# Reefing-BM.net
KiCad netlist of a schematic drawn in Altium Designer
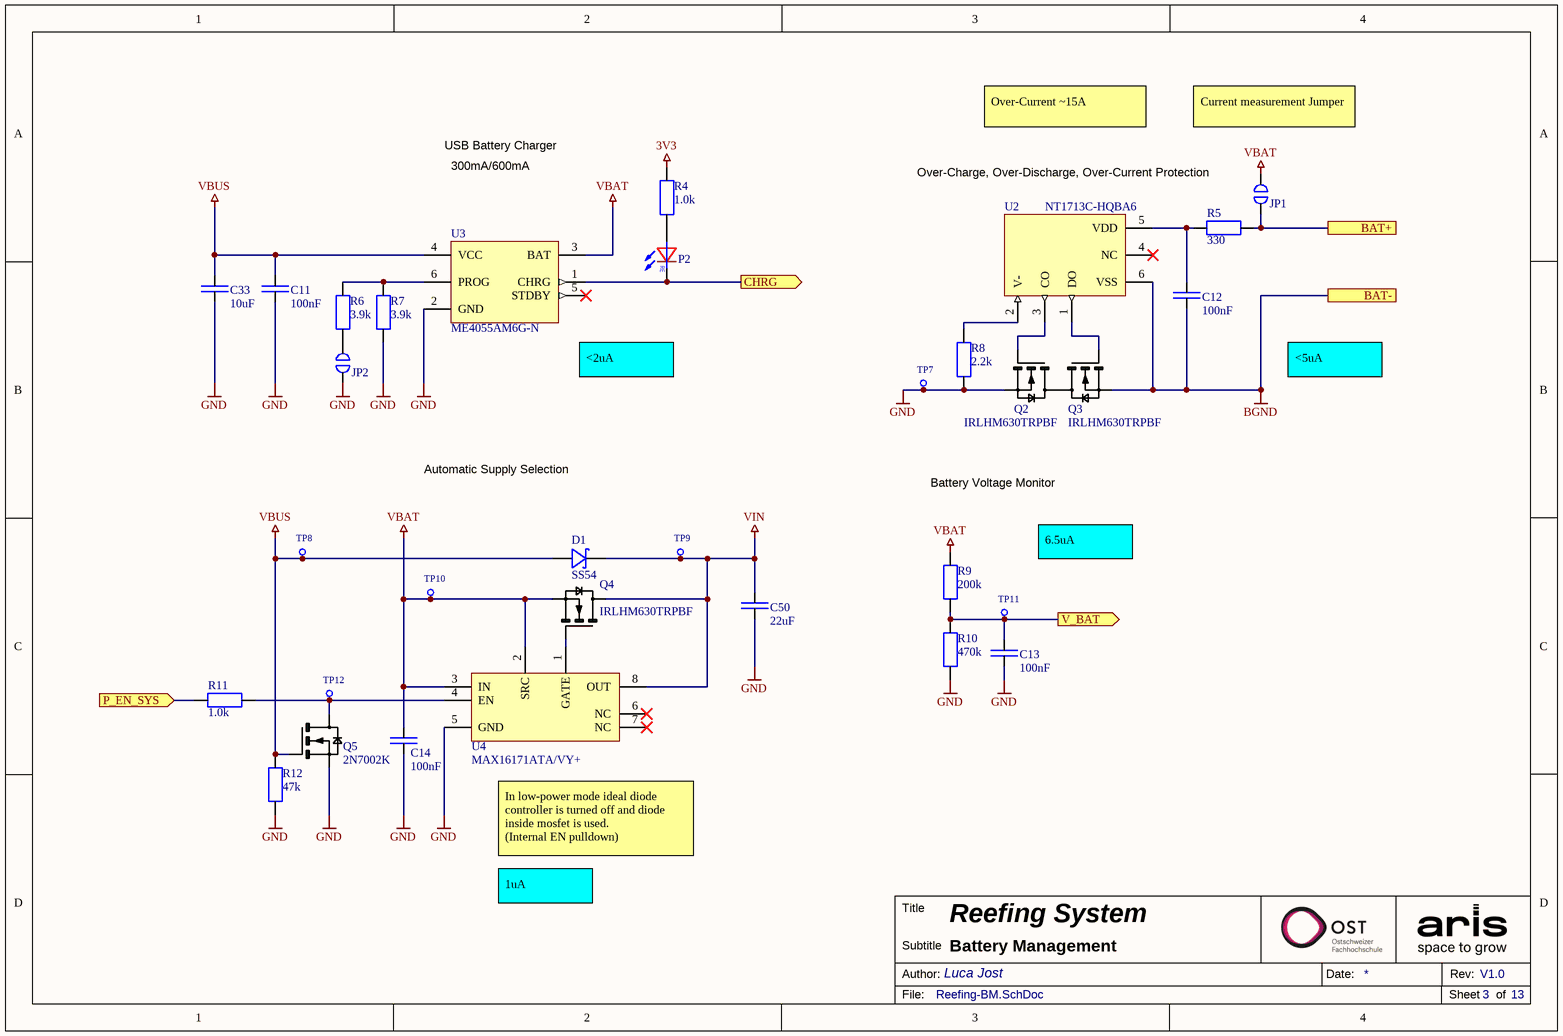
[diagram p0: Reefing-BM.SchDoc]

(export (version "E")
  (design (tool "Eeschema 10.0.6"))
  (components
    (comp (ref "C11")
      (value "100nF")
      (footprint "SMD Keramikkondensator 0402")
      (description "SMD Ceramic Capacitor E6")
      (libsource (lib "Ceramic Capacitors-E6") (part "E6 - 100nF"))
    )
    (comp (ref "C12")
      (value "100nF")
      (footprint "SMD Keramikkondensator 0402")
      (description "SMD Ceramic Capacitor E6")
      (libsource (lib "Ceramic Capacitors-E6") (part "E6 - 100nF"))
    )
    (comp (ref "C13")
      (value "100nF")
      (footprint "SMD Keramikkondensator 0402")
      (description "SMD Ceramic Capacitor E6")
      (libsource (lib "Ceramic Capacitors-E6") (part "E6 - 100nF"))
    )
    (comp (ref "C14")
      (value "100nF")
      (footprint "SMD Keramikkondensator 0402")
      (description "SMD Ceramic Capacitor E6")
      (libsource (lib "Ceramic Capacitors-E6") (part "E6 - 100nF"))
    )
    (comp (ref "C33")
      (value "10uF")
      (footprint "SMD Keramikkondensator 0603")
      (description "SMD Ceramic Capacitor E6")
      (libsource (lib "Ceramic Capacitors-E6") (part "E6 - 10uF"))
    )
    (comp (ref "C50")
      (value "22uF")
      (footprint "SMD Keramikkondensator 0805")
      (description "SMD Ceramic Capacitor E6")
      (libsource (lib "Ceramic Capacitors-E6") (part "E6 - 22uF"))
    )
    (comp (ref "D1")
      (value "SS54")
      (footprint "SMD Diode DO-214-AC")
      (description "40V 5A 550mV @ 5A SMA(DO-214AC) Schottky Barrier Diodes (SBD) ROHS")
      (libsource (lib "Diodes") (part "SS54"))
    )
    (comp (ref "JP1")
      (value "Jumper")
      (footprint "SMD Solder Jumper 1x2mm")
      (description "Single Position Jumper")
      (libsource (lib "Connectors") (part "Jumper-1"))
    )
    (comp (ref "JP2")
      (value "Jumper")
      (footprint "SMD Solder Jumper 1x2mm")
      (description "Single Position Jumper")
      (libsource (lib "Connectors") (part "Jumper-1"))
    )
    (comp (ref "P2")
      (value "LED")
      (footprint "SMD LED 0603")
      (description "Color LED")
      (libsource (lib "Diodes") (part "LED"))
    )
    (comp (ref "Q2")
      (value "IRLHM630TRPBF")
      (footprint "SMD MOSFET DFN 3.3x3.3")
      (description "N-Channel 30V 21A 3.5mOhm@4.5V")
      (libsource (lib "") (part "IRLHM630TRPBF_1"))
    )
    (comp (ref "Q3")
      (value "IRLHM630TRPBF")
      (footprint "SMD MOSFET DFN 3.3x3.3")
      (description "N-Channel 30V 21A 3.5mOhm@4.5V")
      (libsource (lib "Reefing System") (part "IRLHM630TRPBF"))
    )
    (comp (ref "Q4")
      (value "IRLHM630TRPBF")
      (footprint "SMD MOSFET DFN 3.3x3.3")
      (description "N-Channel 30V 21A 3.5mOhm@4.5V")
      (libsource (lib "") (part "IRLHM630TRPBF_2"))
    )
    (comp (ref "Q5")
      (value "2N7002K")
      (footprint "SMD MOSFET SOT-23")
      (description "MOSFET N-Channel 60V / 500mA")
      (libsource (lib "Electronic Switches") (part "2N7002K"))
    )
    (comp (ref "R4")
      (value "1.0k")
      (footprint "SMD Widerstand 0402")
      (description "SMD Chip Resistor E24")
      (libsource (lib "") (part "E24 - 1.0k_1"))
    )
    (comp (ref "R5")
      (value "330")
      (footprint "SMD Widerstand 0402")
      (description "SMD Chip Resistor E24")
      (libsource (lib "Resistors-E24") (part "E24 - 330"))
    )
    (comp (ref "R6")
      (value "3.9k")
      (footprint "SMD Widerstand 0402")
      (description "SMD Chip Resistor E24")
      (libsource (lib "Resistors-E24") (part "E24 - 3.9k"))
    )
    (comp (ref "R7")
      (value "3.9k")
      (footprint "SMD Widerstand 0402")
      (description "SMD Chip Resistor E24")
      (libsource (lib "Resistors-E24") (part "E24 - 3.9k"))
    )
    (comp (ref "R8")
      (value "2.2k")
      (footprint "SMD Widerstand 0402")
      (description "SMD Chip Resistor E24")
      (libsource (lib "Resistors-E24") (part "E24 - 2.2k"))
    )
    (comp (ref "R9")
      (value "200k")
      (footprint "SMD Widerstand 0402")
      (description "SMD Chip Resistor E24")
      (libsource (lib "Resistors-E24") (part "E24 - 200k"))
    )
    (comp (ref "R10")
      (value "470k")
      (footprint "SMD Widerstand 0402")
      (description "SMD Chip Resistor E24")
      (libsource (lib "Resistors-E24") (part "E24 - 470k"))
    )
    (comp (ref "R11")
      (value "1.0k")
      (footprint "SMD Widerstand 0402")
      (description "SMD Chip Resistor E24")
      (libsource (lib "Resistors-E24") (part "E24 - 1.0k"))
    )
    (comp (ref "R12")
      (value "47k")
      (footprint "SMD Widerstand 0402")
      (description "SMD Chip Resistor E24")
      (libsource (lib "Resistors-E24") (part "E24 - 47k"))
    )
    (comp (ref "TP7")
      (value "X-TP")
      (footprint "SMD Testpoint 1mm")
      (description "Testpunkt")
      (libsource (lib "Fleet-Monitor") (part "X-TP"))
    )
    (comp (ref "TP8")
      (value "X-TP")
      (footprint "SMD Testpoint 1mm")
      (description "Testpunkt")
      (libsource (lib "Fleet-Monitor") (part "X-TP"))
    )
    (comp (ref "TP9")
      (value "X-TP")
      (footprint "SMD Testpoint 1mm")
      (description "Testpunkt")
      (libsource (lib "Fleet-Monitor") (part "X-TP"))
    )
    (comp (ref "TP10")
      (value "X-TP")
      (footprint "SMD Testpoint 1mm")
      (description "Testpunkt")
      (libsource (lib "Fleet-Monitor") (part "X-TP"))
    )
    (comp (ref "TP11")
      (value "X-TP")
      (footprint "SMD Testpoint 1mm")
      (description "Testpunkt")
      (libsource (lib "Fleet-Monitor") (part "X-TP"))
    )
    (comp (ref "TP12")
      (value "X-TP")
      (footprint "SMD Testpoint 1mm")
      (description "Testpunkt")
      (libsource (lib "Fleet-Monitor") (part "X-TP"))
    )
    (comp (ref "U2")
      (value "NT1713C-HQBA6")
      (footprint "SMD IC SOT-23-6")
      (description "Protection IC for 1-Cell Battery Pack")
      (libsource (lib "Power Management") (part "NT1713C-HQBA6"))
    )
    (comp (ref "U3")
      (value "ME4055AM6G-N")
      (footprint "SMD IC SOT-23-6")
      (description "800mA Lithium Ion Battery Linear Charger")
      (libsource (lib "Voltage-Converter") (part "ME4055AM6G-N"))
    )
    (comp (ref "U4")
      (value "MAX16171ATA/VY+")
      (footprint "SMD IC TDFN-8")
      (description "OR Controller N+1 ORing Controller N-Channel 1:1 8-TDFN-CU (2x3)")
      (libsource (lib "Power Management") (part "MAX16171ATA/VY+"))
    )
  )
  (nets
    (net (code "1") (name "/BAT+") (class "Default")
      (node (ref "JP1") (pin "2") (pintype "passive"))
      (node (ref "R5") (pin "1") (pinfunction "1_1") (pintype "passive"))
    )
    (net (code "2") (name "/CHRG") (class "Default")
      (node (ref "P2") (pin "K") (pinfunction "K_K") (pintype "passive"))
      (node (ref "U3") (pin "1") (pinfunction "CHRG_1") (pintype "output"))
    )
    (net (code "3") (name "/P_EN_SYS") (class "Default")
      (node (ref "R11") (pin "2") (pinfunction "2_2") (pintype "passive"))
    )
    (net (code "4") (name "/V_BAT") (class "Default")
      (node (ref "C13") (pin "2") (pinfunction "2_2") (pintype "passive"))
      (node (ref "R10") (pin "2") (pinfunction "2_2") (pintype "passive"))
      (node (ref "R9") (pin "1") (pinfunction "1_1") (pintype "passive"))
      (node (ref "TP11") (pin "1") (pinfunction "1_1") (pintype "passive"))
    )
    (net (code "5") (name "3V3") (class "Default")
      (node (ref "R4") (pin "2") (pinfunction "2_2") (pintype "passive"))
    )
    (net (code "6") (name "BGND") (class "Default")
      (node (ref "C12") (pin "1") (pinfunction "1_1") (pintype "passive"))
      (node (ref "Q3") (pin "S") (pinfunction "S_S") (pintype "passive"))
      (node (ref "U2") (pin "6") (pinfunction "VSS_6") (pintype "passive"))
    )
    (net (code "7") (name "GND") (class "Default")
      (node (ref "C11") (pin "1") (pinfunction "1_1") (pintype "passive"))
      (node (ref "C13") (pin "1") (pinfunction "1_1") (pintype "passive"))
      (node (ref "C14") (pin "1") (pinfunction "1_1") (pintype "passive"))
      (node (ref "C33") (pin "1") (pinfunction "1_1") (pintype "passive"))
      (node (ref "C50") (pin "1") (pinfunction "1_1") (pintype "passive"))
      (node (ref "JP2") (pin "2") (pintype "passive"))
      (node (ref "Q2") (pin "S") (pinfunction "S_S") (pintype "passive"))
      (node (ref "Q5") (pin "S") (pinfunction "S_S") (pintype "passive"))
      (node (ref "R10") (pin "1") (pinfunction "1_1") (pintype "passive"))
      (node (ref "R12") (pin "1") (pinfunction "1_1") (pintype "passive"))
      (node (ref "R7") (pin "1") (pinfunction "1_1") (pintype "passive"))
      (node (ref "R8") (pin "1") (pinfunction "1_1") (pintype "passive"))
      (node (ref "TP7") (pin "1") (pinfunction "1_1") (pintype "passive"))
      (node (ref "U3") (pin "2") (pinfunction "GND_2") (pintype "passive"))
      (node (ref "U4") (pin "5") (pinfunction "GND_5") (pintype "passive"))
    )
    (net (code "8") (name "Net-(JP2-Pad1)") (class "Default")
      (node (ref "JP2") (pin "1") (pintype "passive"))
      (node (ref "R6") (pin "1") (pinfunction "1_1") (pintype "passive"))
    )
    (net (code "9") (name "Net-(P2-PadA)") (class "Default")
      (node (ref "P2") (pin "A") (pinfunction "A_A") (pintype "passive"))
      (node (ref "R4") (pin "1") (pinfunction "1_1") (pintype "passive"))
    )
    (net (code "10") (name "Net-(Q2-PadD)") (class "Default")
      (node (ref "Q2") (pin "D") (pinfunction "D_D") (pintype "passive"))
      (node (ref "Q3") (pin "D") (pinfunction "D_D") (pintype "passive"))
    )
    (net (code "11") (name "Net-(U2-CO)") (class "Default")
      (node (ref "Q2") (pin "G") (pinfunction "G_G") (pintype "passive"))
      (node (ref "U2") (pin "3") (pinfunction "CO_3") (pintype "output"))
    )
    (net (code "12") (name "Net-(U2-DO)") (class "Default")
      (node (ref "Q3") (pin "G") (pinfunction "G_G") (pintype "passive"))
      (node (ref "U2") (pin "1") (pinfunction "DO_1") (pintype "output"))
    )
    (net (code "13") (name "Net-(U2-V-)") (class "Default")
      (node (ref "R8") (pin "2") (pinfunction "2_2") (pintype "passive"))
      (node (ref "U2") (pin "2") (pinfunction "V-_2") (pintype "input"))
    )
    (net (code "14") (name "Net-(U2-VDD)") (class "Default")
      (node (ref "C12") (pin "2") (pinfunction "2_2") (pintype "passive"))
      (node (ref "R5") (pin "2") (pinfunction "2_2") (pintype "passive"))
      (node (ref "U2") (pin "5") (pinfunction "VDD_5") (pintype "passive"))
    )
    (net (code "15") (name "Net-(U3-PROG)") (class "Default")
      (node (ref "R6") (pin "2") (pinfunction "2_2") (pintype "passive"))
      (node (ref "R7") (pin "2") (pinfunction "2_2") (pintype "passive"))
      (node (ref "U3") (pin "6") (pinfunction "PROG_6") (pintype "passive"))
    )
    (net (code "16") (name "Net-(U4-EN)") (class "Default")
      (node (ref "Q5") (pin "D") (pinfunction "D_D") (pintype "passive"))
      (node (ref "R11") (pin "1") (pinfunction "1_1") (pintype "passive"))
      (node (ref "TP12") (pin "1") (pinfunction "1_1") (pintype "passive"))
      (node (ref "U4") (pin "4") (pinfunction "EN_4") (pintype "passive"))
    )
    (net (code "17") (name "Net-(U4-GATE)") (class "Default")
      (node (ref "Q4") (pin "G") (pinfunction "G_G") (pintype "passive"))
      (node (ref "U4") (pin "1") (pinfunction "GATE_1") (pintype "passive"))
    )
    (net (code "18") (name "VBAT") (class "Default")
      (node (ref "C14") (pin "2") (pinfunction "2_2") (pintype "passive"))
      (node (ref "JP1") (pin "1") (pintype "passive"))
      (node (ref "Q4") (pin "S") (pinfunction "S_S") (pintype "passive"))
      (node (ref "R9") (pin "2") (pinfunction "2_2") (pintype "passive"))
      (node (ref "TP10") (pin "1") (pinfunction "1_1") (pintype "passive"))
      (node (ref "U3") (pin "3") (pinfunction "BAT_3") (pintype "passive"))
      (node (ref "U4") (pin "2") (pinfunction "SRC_2") (pintype "passive"))
      (node (ref "U4") (pin "3") (pinfunction "IN_3") (pintype "passive"))
    )
    (net (code "19") (name "VBUS") (class "Default")
      (node (ref "C11") (pin "2") (pinfunction "2_2") (pintype "passive"))
      (node (ref "C33") (pin "2") (pinfunction "2_2") (pintype "passive"))
      (node (ref "D1") (pin "A") (pinfunction "A_A") (pintype "passive"))
      (node (ref "Q5") (pin "G") (pinfunction "G_G") (pintype "passive"))
      (node (ref "R12") (pin "2") (pinfunction "2_2") (pintype "passive"))
      (node (ref "TP8") (pin "1") (pinfunction "1_1") (pintype "passive"))
      (node (ref "U3") (pin "4") (pinfunction "VCC_4") (pintype "passive"))
    )
    (net (code "20") (name "VIN") (class "Default")
      (node (ref "C50") (pin "2") (pinfunction "2_2") (pintype "passive"))
      (node (ref "D1") (pin "K") (pinfunction "K_K") (pintype "passive"))
      (node (ref "Q4") (pin "D") (pinfunction "D_D") (pintype "passive"))
      (node (ref "TP9") (pin "1") (pinfunction "1_1") (pintype "passive"))
      (node (ref "U4") (pin "8") (pinfunction "OUT_8") (pintype "passive"))
    )
    (net (code "21") (name "unconnected-(U2-NC-Pad4)") (class "Default")
      (node (ref "U2") (pin "4") (pinfunction "NC_4") (pintype "passive+no_connect"))
    )
    (net (code "22") (name "unconnected-(U3-STDBY-Pad5)") (class "Default")
      (node (ref "U3") (pin "5") (pinfunction "STDBY_5") (pintype "output+no_connect"))
    )
    (net (code "23") (name "unconnected-(U4-NC-Pad6)") (class "Default")
      (node (ref "U4") (pin "6") (pinfunction "NC_6") (pintype "passive+no_connect"))
    )
    (net (code "24") (name "unconnected-(U4-NC-Pad7)") (class "Default")
      (node (ref "U4") (pin "7") (pinfunction "NC_7") (pintype "passive+no_connect"))
    )
  )
)
